# CAN_Transceiver.net
KiCad netlist of a schematic drawn in Altium Designer
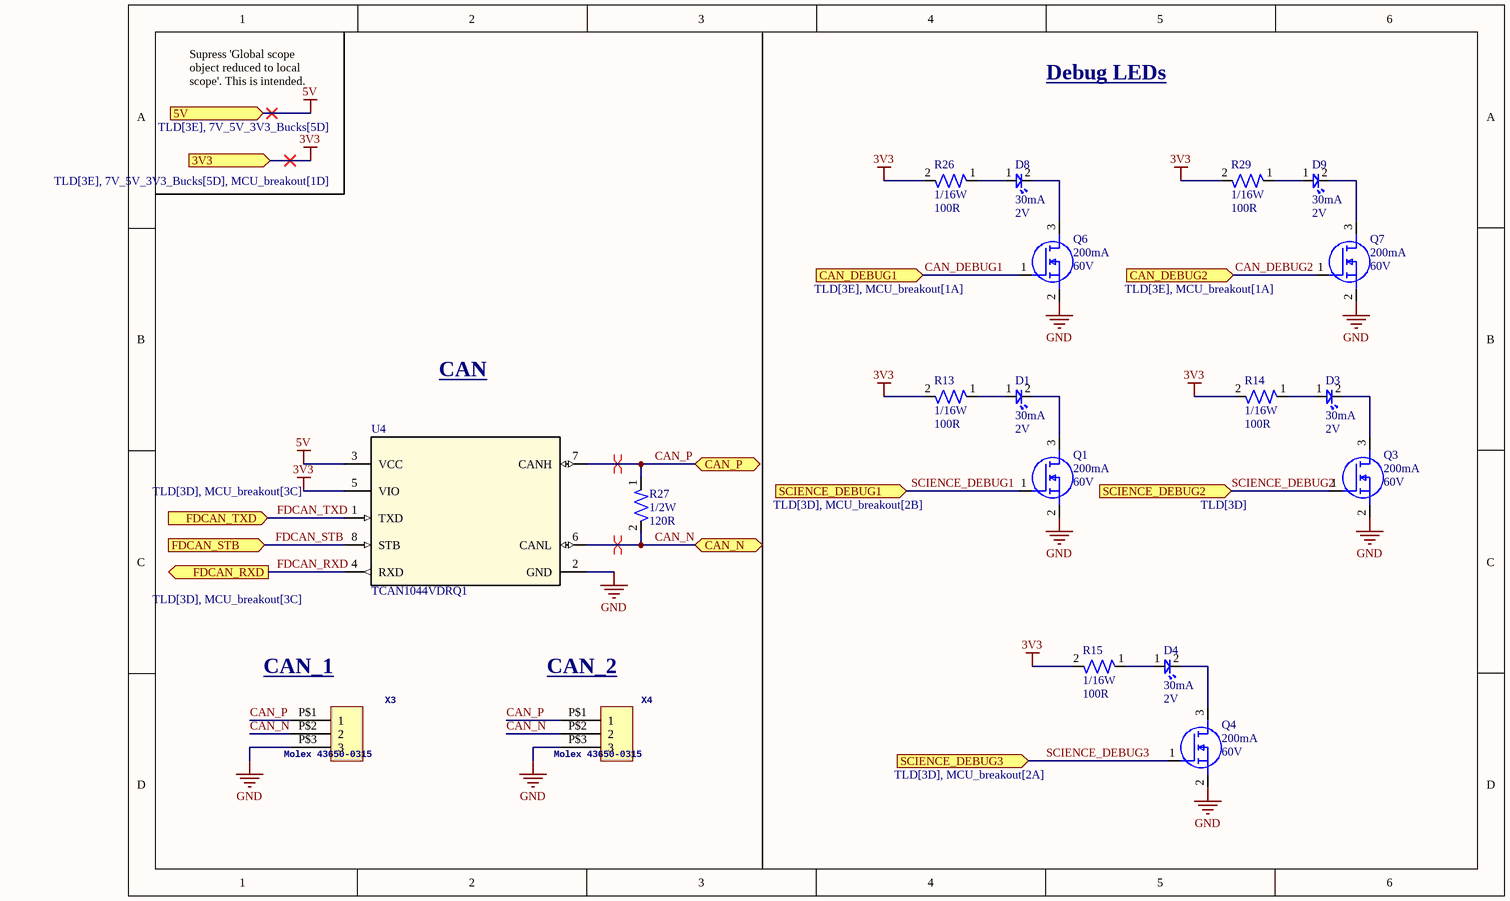
[diagram p0: CAN_Transceiver.SchDoc]

(export (version "E")
  (design (tool "Eeschema 10.0.6"))
  (components
    (comp (ref "D1")
      (value "BL-HKC36G-AV-TRB")
      (footprint "LED-0603")
      (description "LED YELLOW CLEAR 0603 SMD")
      (fields (field (name "FORWARD CURRENT") "30mA") (field (name "FORWARD VOLTAGE") "2V"))
      (libsource (lib "JLC_25") (part "LED-0001"))
    )
    (comp (ref "D3")
      (value "BL-HKC36G-AV-TRB")
      (footprint "LED-0603")
      (description "LED YELLOW CLEAR 0603 SMD")
      (fields (field (name "FORWARD CURRENT") "30mA") (field (name "FORWARD VOLTAGE") "2V"))
      (libsource (lib "JLC_25") (part "LED-0001"))
    )
    (comp (ref "D4")
      (value "BL-HKC36G-AV-TRB")
      (footprint "LED-0603")
      (description "LED YELLOW CLEAR 0603 SMD")
      (fields (field (name "FORWARD CURRENT") "30mA") (field (name "FORWARD VOLTAGE") "2V"))
      (libsource (lib "JLC_25") (part "LED-0001"))
    )
    (comp (ref "D8")
      (value "BL-HKC36G-AV-TRB")
      (footprint "LED-0603")
      (description "LED YELLOW CLEAR 0603 SMD")
      (fields (field (name "FORWARD CURRENT") "30mA") (field (name "FORWARD VOLTAGE") "2V"))
      (libsource (lib "JLC_25") (part "LED-0001"))
    )
    (comp (ref "D9")
      (value "BL-HKC36G-AV-TRB")
      (footprint "LED-0603")
      (description "LED YELLOW CLEAR 0603 SMD")
      (fields (field (name "FORWARD CURRENT") "30mA") (field (name "FORWARD VOLTAGE") "2V"))
      (libsource (lib "JLC_25") (part "LED-0001"))
    )
    (comp (ref "Q1")
      (value "T2N7002AK,LM")
      (footprint "IC-SOT23-3")
      (description "MOSFET N-CH 60V 200MA SOT23")
      (fields (field (name "CONTINUOUS CURRENT") "200mA") (field (name "VOLTAGE") "60V"))
      (libsource (lib "JLC_25") (part "NMOS-200MA-0001"))
    )
    (comp (ref "Q3")
      (value "T2N7002AK,LM")
      (footprint "IC-SOT23-3")
      (description "MOSFET N-CH 60V 200MA SOT23")
      (fields (field (name "CONTINUOUS CURRENT") "200mA") (field (name "VOLTAGE") "60V"))
      (libsource (lib "JLC_25") (part "NMOS-200MA-0001"))
    )
    (comp (ref "Q4")
      (value "T2N7002AK,LM")
      (footprint "IC-SOT23-3")
      (description "MOSFET N-CH 60V 200MA SOT23")
      (fields (field (name "CONTINUOUS CURRENT") "200mA") (field (name "VOLTAGE") "60V"))
      (libsource (lib "JLC_25") (part "NMOS-200MA-0001"))
    )
    (comp (ref "Q6")
      (value "T2N7002AK,LM")
      (footprint "IC-SOT23-3")
      (description "MOSFET N-CH 60V 200MA SOT23")
      (fields (field (name "CONTINUOUS CURRENT") "200mA") (field (name "VOLTAGE") "60V"))
      (libsource (lib "JLC_25") (part "NMOS-200MA-0001"))
    )
    (comp (ref "Q7")
      (value "T2N7002AK,LM")
      (footprint "IC-SOT23-3")
      (description "MOSFET N-CH 60V 200MA SOT23")
      (fields (field (name "CONTINUOUS CURRENT") "200mA") (field (name "VOLTAGE") "60V"))
      (libsource (lib "JLC_25") (part "NMOS-200MA-0001"))
    )
    (comp (ref "R13")
      (value "RC0402FR-07100RL")
      (footprint "RES-0402")
      (description "RES 100 OHM 1% 1/16W 0402")
      (fields
        (field (name "TOLERANCE") "1%")
        (field (name "POWER") "1/16W")
        (field (name "RESISTANCE") "100R")
      )
      (libsource (lib "JLC_25") (part "RES-100-0001"))
    )
    (comp (ref "R14")
      (value "RC0402FR-07100RL")
      (footprint "RES-0402")
      (description "RES 100 OHM 1% 1/16W 0402")
      (fields
        (field (name "TOLERANCE") "1%")
        (field (name "POWER") "1/16W")
        (field (name "RESISTANCE") "100R")
      )
      (libsource (lib "JLC_25") (part "RES-100-0001"))
    )
    (comp (ref "R15")
      (value "RC0402FR-07100RL")
      (footprint "RES-0402")
      (description "RES 100 OHM 1% 1/16W 0402")
      (fields
        (field (name "TOLERANCE") "1%")
        (field (name "POWER") "1/16W")
        (field (name "RESISTANCE") "100R")
      )
      (libsource (lib "JLC_25") (part "RES-100-0001"))
    )
    (comp (ref "R26")
      (value "RC0402FR-07100RL")
      (footprint "RES-0402")
      (description "RES 100 OHM 1% 1/16W 0402")
      (fields
        (field (name "TOLERANCE") "1%")
        (field (name "POWER") "1/16W")
        (field (name "RESISTANCE") "100R")
      )
      (libsource (lib "JLC_25") (part "RES-100-0001"))
    )
    (comp (ref "R27")
      (value "RC1210FR-07120RL")
      (footprint "RES-1210")
      (description "RES 120 OHM 1% 1/2W 1210")
      (fields
        (field (name "TOLERANCE") "1%")
        (field (name "POWER") "1/2W")
        (field (name "RESISTANCE") "120R")
      )
      (libsource (lib "JLC_25") (part "RES-120-0001"))
    )
    (comp (ref "R29")
      (value "RC0402FR-07100RL")
      (footprint "RES-0402")
      (description "RES 100 OHM 1% 1/16W 0402")
      (fields
        (field (name "TOLERANCE") "1%")
        (field (name "POWER") "1/16W")
        (field (name "RESISTANCE") "100R")
      )
      (libsource (lib "JLC_25") (part "RES-100-0001"))
    )
    (comp (ref "U4")
      (value "TCAN1044VDRQ1")
      (footprint "IC-8SOIC")
      (description "IC TRANSCEIVER 1/1 8SOIC")
      (libsource (lib "JLC_25") (part "IC-CAN-0001"))
    )
    (comp (ref "X3")
      (value "Molex 43650-0315")
      (footprint "43650-0315")
      (libsource (lib "JLC_25") (part "Micro-Fit Molex 3 Pin Vertical"))
    )
    (comp (ref "X4")
      (value "Molex 43650-0315")
      (footprint "43650-0315")
      (libsource (lib "JLC_25") (part "Micro-Fit Molex 3 Pin Vertical"))
    )
  )
  (nets
    (net (code "1") (name "/CAN_DEBUG1") (class "Default")
      (node (ref "Q6") (pin "1") (pinfunction "G_1") (pintype "passive"))
    )
    (net (code "2") (name "/CAN_DEBUG2") (class "Default")
      (node (ref "Q7") (pin "1") (pinfunction "G_1") (pintype "passive"))
    )
    (net (code "3") (name "/CAN_N") (class "Default")
      (node (ref "R27") (pin "2") (pinfunction "2_2") (pintype "passive"))
      (node (ref "U4") (pin "6") (pinfunction "CANL_6") (pintype "bidirectional"))
      (node (ref "X3") (pin "P$2") (pinfunction "2_P$2") (pintype "passive"))
      (node (ref "X4") (pin "P$2") (pinfunction "2_P$2") (pintype "passive"))
    )
    (net (code "4") (name "/CAN_P") (class "Default")
      (node (ref "R27") (pin "1") (pinfunction "1_1") (pintype "passive"))
      (node (ref "U4") (pin "7") (pinfunction "CANH_7") (pintype "bidirectional"))
      (node (ref "X3") (pin "P$1") (pinfunction "1_P$1") (pintype "passive"))
      (node (ref "X4") (pin "P$1") (pinfunction "1_P$1") (pintype "passive"))
    )
    (net (code "5") (name "/FDCAN_RXD") (class "Default")
      (node (ref "U4") (pin "4") (pinfunction "RXD_4") (pintype "output"))
    )
    (net (code "6") (name "/FDCAN_STB") (class "Default")
      (node (ref "U4") (pin "8") (pinfunction "STB_8") (pintype "input"))
    )
    (net (code "7") (name "/FDCAN_TXD") (class "Default")
      (node (ref "U4") (pin "1") (pinfunction "TXD_1") (pintype "input"))
    )
    (net (code "8") (name "/SCIENCE_DEBUG1") (class "Default")
      (node (ref "Q1") (pin "1") (pinfunction "G_1") (pintype "passive"))
    )
    (net (code "9") (name "/SCIENCE_DEBUG2") (class "Default")
      (node (ref "Q3") (pin "1") (pinfunction "G_1") (pintype "passive"))
    )
    (net (code "10") (name "/SCIENCE_DEBUG3") (class "Default")
      (node (ref "Q4") (pin "1") (pinfunction "G_1") (pintype "passive"))
    )
    (net (code "11") (name "3V3") (class "Default")
      (node (ref "R13") (pin "2") (pinfunction "2_2") (pintype "passive"))
      (node (ref "R14") (pin "2") (pinfunction "2_2") (pintype "passive"))
      (node (ref "R15") (pin "2") (pinfunction "2_2") (pintype "passive"))
      (node (ref "R26") (pin "2") (pinfunction "2_2") (pintype "passive"))
      (node (ref "R29") (pin "2") (pinfunction "2_2") (pintype "passive"))
      (node (ref "U4") (pin "5") (pinfunction "VIO_5") (pintype "power_in"))
    )
    (net (code "12") (name "5V") (class "Default")
      (node (ref "U4") (pin "3") (pinfunction "VCC_3") (pintype "power_in"))
    )
    (net (code "13") (name "GND") (class "Default")
      (node (ref "Q1") (pin "2") (pinfunction "S_2") (pintype "passive"))
      (node (ref "Q3") (pin "2") (pinfunction "S_2") (pintype "passive"))
      (node (ref "Q4") (pin "2") (pinfunction "S_2") (pintype "passive"))
      (node (ref "Q6") (pin "2") (pinfunction "S_2") (pintype "passive"))
      (node (ref "Q7") (pin "2") (pinfunction "S_2") (pintype "passive"))
      (node (ref "U4") (pin "2") (pinfunction "GND_2") (pintype "power_in"))
      (node (ref "X3") (pin "P$3") (pinfunction "3_P$3") (pintype "passive"))
      (node (ref "X4") (pin "P$3") (pinfunction "3_P$3") (pintype "passive"))
    )
    (net (code "14") (name "Net-(D1-Pad1)") (class "Default")
      (node (ref "D1") (pin "1") (pinfunction "1_1") (pintype "passive"))
      (node (ref "R13") (pin "1") (pinfunction "1_1") (pintype "passive"))
    )
    (net (code "15") (name "Net-(D3-Pad1)") (class "Default")
      (node (ref "D3") (pin "1") (pinfunction "1_1") (pintype "passive"))
      (node (ref "R14") (pin "1") (pinfunction "1_1") (pintype "passive"))
    )
    (net (code "16") (name "Net-(D4-Pad1)") (class "Default")
      (node (ref "D4") (pin "1") (pinfunction "1_1") (pintype "passive"))
      (node (ref "R15") (pin "1") (pinfunction "1_1") (pintype "passive"))
    )
    (net (code "17") (name "Net-(D8-Pad1)") (class "Default")
      (node (ref "D8") (pin "1") (pinfunction "1_1") (pintype "passive"))
      (node (ref "R26") (pin "1") (pinfunction "1_1") (pintype "passive"))
    )
    (net (code "18") (name "Net-(D9-Pad1)") (class "Default")
      (node (ref "D9") (pin "1") (pinfunction "1_1") (pintype "passive"))
      (node (ref "R29") (pin "1") (pinfunction "1_1") (pintype "passive"))
    )
    (net (code "19") (name "Net-(Q1-D)") (class "Default")
      (node (ref "D1") (pin "2") (pinfunction "2_2") (pintype "passive"))
      (node (ref "Q1") (pin "3") (pinfunction "D_3") (pintype "passive"))
    )
    (net (code "20") (name "Net-(Q3-D)") (class "Default")
      (node (ref "D3") (pin "2") (pinfunction "2_2") (pintype "passive"))
      (node (ref "Q3") (pin "3") (pinfunction "D_3") (pintype "passive"))
    )
    (net (code "21") (name "Net-(Q4-D)") (class "Default")
      (node (ref "D4") (pin "2") (pinfunction "2_2") (pintype "passive"))
      (node (ref "Q4") (pin "3") (pinfunction "D_3") (pintype "passive"))
    )
    (net (code "22") (name "Net-(Q6-D)") (class "Default")
      (node (ref "D8") (pin "2") (pinfunction "2_2") (pintype "passive"))
      (node (ref "Q6") (pin "3") (pinfunction "D_3") (pintype "passive"))
    )
    (net (code "23") (name "Net-(Q7-D)") (class "Default")
      (node (ref "D9") (pin "2") (pinfunction "2_2") (pintype "passive"))
      (node (ref "Q7") (pin "3") (pinfunction "D_3") (pintype "passive"))
    )
  )
)
